# Schematic_v13.net
KiCad netlist of a schematic drawn in EAGLE
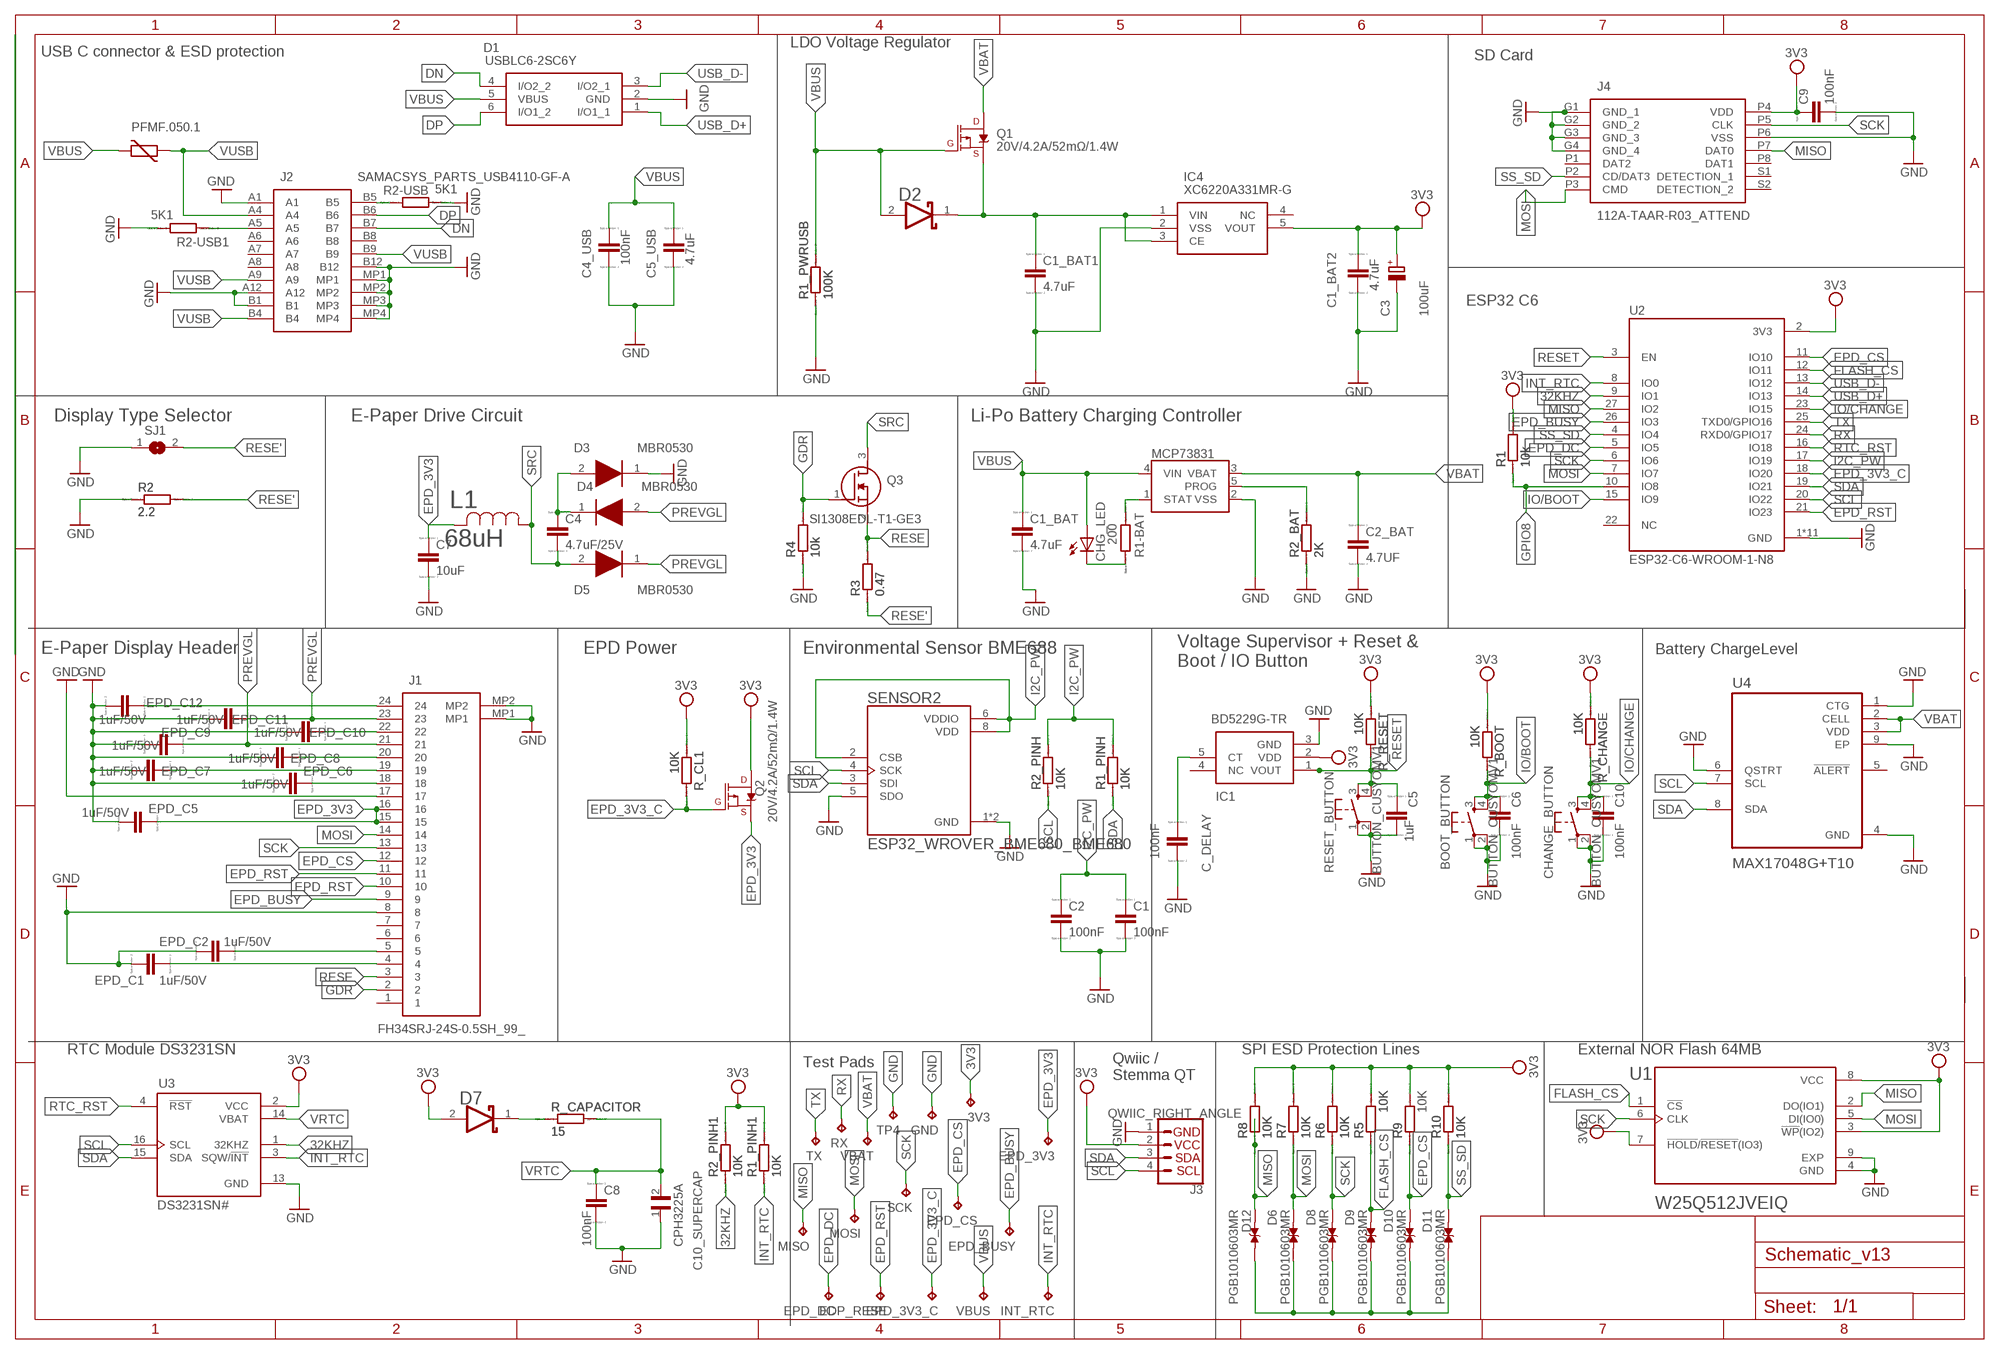
[diagram p0: schematic, sheet 1]

(export (version "E")
  (design (tool "Eeschema 10.0.6"))
  (components
    (comp (ref "3V3")
      (value "TPTP20R")
      (footprint "eagle-import:TP20R")
      (libsource (lib "eagle-import") (part "TPTP20R"))
    )
    (comp (ref "BOOT_BUTTON")
      (value "BUTTON_CUSYOMV1")
      (footprint "eagle-import:MYBUTTON")
      (libsource (lib "eagle-import") (part "BUTTON_CUSYOMV1"))
    )
    (comp (ref "C1")
      (value "100nF")
      (footprint "eagle-import:ESP32_WROVER_EAGLE-LTSPICE_C0402")
      (libsource (lib "eagle-import") (part "ESP32_WROVER_EAGLE-LTSPICE_CC0402"))
    )
    (comp (ref "C1_BAT")
      (value "4.7uF")
      (footprint "eagle-import:ESP32_WROVER_EAGLE-LTSPICE_C0402")
      (libsource (lib "eagle-import") (part "ESP32_WROVER_EAGLE-LTSPICE_CC0402"))
    )
    (comp (ref "C1_BAT1")
      (value "4.7uF")
      (footprint "eagle-import:ESP32_WROVER_EAGLE-LTSPICE_C0402")
      (libsource (lib "eagle-import") (part "ESP32_WROVER_EAGLE-LTSPICE_CC0402"))
    )
    (comp (ref "C1_BAT2")
      (value "4.7uF")
      (footprint "eagle-import:ESP32_WROVER_EAGLE-LTSPICE_C0402")
      (libsource (lib "eagle-import") (part "ESP32_WROVER_EAGLE-LTSPICE_CC0402"))
    )
    (comp (ref "C2")
      (value "100nF")
      (footprint "eagle-import:ESP32_WROVER_EAGLE-LTSPICE_C0402")
      (libsource (lib "eagle-import") (part "ESP32_WROVER_EAGLE-LTSPICE_CC0402"))
    )
    (comp (ref "C2_BAT")
      (value "4.7UF")
      (footprint "eagle-import:ESP32_WROVER_EAGLE-LTSPICE_C0402")
      (libsource (lib "eagle-import") (part "ESP32_WROVER_EAGLE-LTSPICE_CC0402"))
    )
    (comp (ref "C3")
      (value "100uF")
      (footprint "eagle-import:RCL_CT3528")
      (libsource (lib "eagle-import") (part "RCL_CPOL-EUCT3528"))
    )
    (comp (ref "C4")
      (value "4.7uF/25V")
      (footprint "eagle-import:ESP32_WROVER_EAGLE-LTSPICE_C0402")
      (libsource (lib "eagle-import") (part "ESP32_WROVER_EAGLE-LTSPICE_CC0402"))
    )
    (comp (ref "C4_USB")
      (value "100nF")
      (footprint "eagle-import:ESP32_WROVER_EAGLE-LTSPICE_C0402")
      (libsource (lib "eagle-import") (part "ESP32_WROVER_EAGLE-LTSPICE_CC0402"))
    )
    (comp (ref "C5")
      (value "1uF")
      (footprint "eagle-import:ESP32_WROVER_EAGLE-LTSPICE_C0402")
      (libsource (lib "eagle-import") (part "ESP32_WROVER_EAGLE-LTSPICE_CC0402"))
    )
    (comp (ref "C5_USB")
      (value "4.7uF")
      (footprint "eagle-import:ESP32_WROVER_EAGLE-LTSPICE_C0402")
      (libsource (lib "eagle-import") (part "ESP32_WROVER_EAGLE-LTSPICE_CC0402"))
    )
    (comp (ref "C6")
      (value "100nF")
      (footprint "eagle-import:ESP32_WROVER_EAGLE-LTSPICE_C0402")
      (libsource (lib "eagle-import") (part "ESP32_WROVER_EAGLE-LTSPICE_CC0402"))
    )
    (comp (ref "C7")
      (value "10uF")
      (footprint "eagle-import:ESP32_WROVER_EAGLE-LTSPICE_C0402")
      (libsource (lib "eagle-import") (part "ESP32_WROVER_EAGLE-LTSPICE_CC0402"))
    )
    (comp (ref "C8")
      (value "100nF")
      (footprint "eagle-import:ESP32_WROVER_EAGLE-LTSPICE_C0402")
      (libsource (lib "eagle-import") (part "ESP32_WROVER_EAGLE-LTSPICE_CC0402"))
    )
    (comp (ref "C9")
      (value "100nF")
      (footprint "eagle-import:ESP32_WROVER_EAGLE-LTSPICE_C0402")
      (libsource (lib "eagle-import") (part "ESP32_WROVER_EAGLE-LTSPICE_CC0402"))
    )
    (comp (ref "C10")
      (value "100nF")
      (footprint "eagle-import:ESP32_WROVER_EAGLE-LTSPICE_C0402")
      (libsource (lib "eagle-import") (part "ESP32_WROVER_EAGLE-LTSPICE_CC0402"))
    )
    (comp (ref "C10_SUPERCAP")
      (value "CPH3225A")
      (footprint "eagle-import:CAPCP3225X100N")
      (fields (field (name "MF") "Seiko Instruments"))
      (libsource (lib "eagle-import") (part "CPH3225A"))
    )
    (comp (ref "CHANGE_BUTTON")
      (value "BUTTON_CUSYOMV1")
      (footprint "eagle-import:MYBUTTON")
      (libsource (lib "eagle-import") (part "BUTTON_CUSYOMV1"))
    )
    (comp (ref "CHG_LED")
      (value "ADAFRUIT_LEDCHIP-LED0603")
      (footprint "eagle-import:ADAFRUIT_CHIP-LED0603")
      (libsource (lib "eagle-import") (part "ADAFRUIT_LEDCHIP-LED0603"))
    )
    (comp (ref "C_DELAY")
      (value "100nF")
      (footprint "eagle-import:ESP32_WROVER_EAGLE-LTSPICE_C0402")
      (libsource (lib "eagle-import") (part "ESP32_WROVER_EAGLE-LTSPICE_CC0402"))
    )
    (comp (ref "D1")
      (value "USBLC6-2SC6Y")
      (footprint "eagle-import:SOT95P280X145-6N")
      (fields (field (name "MF") "STMicroelectronics"))
      (libsource (lib "eagle-import") (part "USBLC6-2SC6Y"))
    )
    (comp (ref "D2")
      (value "ESP32_WROVER_AVX---SD0805S020S1R0_AVX_SD0805S020S1R0_0_0AVX_SD0805S020S1R0_0_0")
      (footprint "eagle-import:ESP32_WROVER_AVX---SD0805S020S1R0_AVX_SD0805S020S1R0_0")
      (fields
        (field (name "DIGIKEY_PART_NUMBER") "478-7800-1-ND")
        (field (name "MF") "AVX")
        (field (name "MOUSER_PART_NUMBER") "581-SD0805S020S1R0")
      )
      (libsource (lib "eagle-import") (part "ESP32_WROVER_AVX---SD0805S020S1R0_AVX_SD0805S020S1R0_0_0AVX_SD0805S020S1R0_0_0"))
    )
    (comp (ref "D3")
      (value "MBR0530")
      (footprint "eagle-import:SOD3716X135N")
      (fields (field (name "MF") "ON Semiconductor"))
      (libsource (lib "eagle-import") (part "MBR0530"))
    )
    (comp (ref "D4")
      (value "MBR0530")
      (footprint "eagle-import:SOD3716X135N")
      (fields (field (name "MF") "ON Semiconductor"))
      (libsource (lib "eagle-import") (part "MBR0530"))
    )
    (comp (ref "D5")
      (value "MBR0530")
      (footprint "eagle-import:SOD3716X135N")
      (fields (field (name "MF") "ON Semiconductor"))
      (libsource (lib "eagle-import") (part "MBR0530"))
    )
    (comp (ref "D6")
      (value "PGB1010603MR")
      (footprint "eagle-import:DIOC1608X36N")
      (fields (field (name "MF") "Littelfuse Inc."))
      (libsource (lib "eagle-import") (part "PGB1010603MR"))
    )
    (comp (ref "D7")
      (value "ESP32_WROVER_AVX---SD0805S020S1R0_AVX_SD0805S020S1R0_0_0AVX_SD0805S020S1R0_0_0")
      (footprint "eagle-import:ESP32_WROVER_AVX---SD0805S020S1R0_AVX_SD0805S020S1R0_0")
      (fields
        (field (name "DIGIKEY_PART_NUMBER") "478-7800-1-ND")
        (field (name "MF") "AVX")
        (field (name "MOUSER_PART_NUMBER") "581-SD0805S020S1R0")
      )
      (libsource (lib "eagle-import") (part "ESP32_WROVER_AVX---SD0805S020S1R0_AVX_SD0805S020S1R0_0_0AVX_SD0805S020S1R0_0_0"))
    )
    (comp (ref "D8")
      (value "PGB1010603MR")
      (footprint "eagle-import:DIOC1608X36N")
      (fields (field (name "MF") "Littelfuse Inc."))
      (libsource (lib "eagle-import") (part "PGB1010603MR"))
    )
    (comp (ref "D9")
      (value "PGB1010603MR")
      (footprint "eagle-import:DIOC1608X36N")
      (fields (field (name "MF") "Littelfuse Inc."))
      (libsource (lib "eagle-import") (part "PGB1010603MR"))
    )
    (comp (ref "D10")
      (value "PGB1010603MR")
      (footprint "eagle-import:DIOC1608X36N")
      (fields (field (name "MF") "Littelfuse Inc."))
      (libsource (lib "eagle-import") (part "PGB1010603MR"))
    )
    (comp (ref "D11")
      (value "PGB1010603MR")
      (footprint "eagle-import:DIOC1608X36N")
      (fields (field (name "MF") "Littelfuse Inc."))
      (libsource (lib "eagle-import") (part "PGB1010603MR"))
    )
    (comp (ref "D12")
      (value "PGB1010603MR")
      (footprint "eagle-import:DIOC1608X36N")
      (fields (field (name "MF") "Littelfuse Inc."))
      (libsource (lib "eagle-import") (part "PGB1010603MR"))
    )
    (comp (ref "EDP_RESE")
      (value "TPTP20R")
      (footprint "eagle-import:TP20R")
      (libsource (lib "eagle-import") (part "TPTP20R"))
    )
    (comp (ref "EPD_3V3")
      (value "TPTP20R")
      (footprint "eagle-import:TP20R")
      (libsource (lib "eagle-import") (part "TPTP20R"))
    )
    (comp (ref "EPD_3V3_C")
      (value "TPTP20R")
      (footprint "eagle-import:TP20R")
      (libsource (lib "eagle-import") (part "TPTP20R"))
    )
    (comp (ref "EPD_BUSY")
      (value "TPTP20R")
      (footprint "eagle-import:TP20R")
      (libsource (lib "eagle-import") (part "TPTP20R"))
    )
    (comp (ref "EPD_C1")
      (value "1uF/50V")
      (footprint "eagle-import:ESP32_WROVER_EAGLE-LTSPICE_C0402")
      (libsource (lib "eagle-import") (part "ESP32_WROVER_EAGLE-LTSPICE_CC0402"))
    )
    (comp (ref "EPD_C2")
      (value "1uF/50V")
      (footprint "eagle-import:ESP32_WROVER_EAGLE-LTSPICE_C0402")
      (libsource (lib "eagle-import") (part "ESP32_WROVER_EAGLE-LTSPICE_CC0402"))
    )
    (comp (ref "EPD_C5")
      (value "1uF/50V")
      (footprint "eagle-import:ESP32_WROVER_EAGLE-LTSPICE_C0402")
      (libsource (lib "eagle-import") (part "ESP32_WROVER_EAGLE-LTSPICE_CC0402"))
    )
    (comp (ref "EPD_C6")
      (value "1uF/50V")
      (footprint "eagle-import:ESP32_WROVER_EAGLE-LTSPICE_C0402")
      (libsource (lib "eagle-import") (part "ESP32_WROVER_EAGLE-LTSPICE_CC0402"))
    )
    (comp (ref "EPD_C7")
      (value "1uF/50V")
      (footprint "eagle-import:ESP32_WROVER_EAGLE-LTSPICE_C0402")
      (libsource (lib "eagle-import") (part "ESP32_WROVER_EAGLE-LTSPICE_CC0402"))
    )
    (comp (ref "EPD_C8")
      (value "1uF/50V")
      (footprint "eagle-import:ESP32_WROVER_EAGLE-LTSPICE_C0402")
      (libsource (lib "eagle-import") (part "ESP32_WROVER_EAGLE-LTSPICE_CC0402"))
    )
    (comp (ref "EPD_C9")
      (value "1uF/50V")
      (footprint "eagle-import:ESP32_WROVER_EAGLE-LTSPICE_C0402")
      (libsource (lib "eagle-import") (part "ESP32_WROVER_EAGLE-LTSPICE_CC0402"))
    )
    (comp (ref "EPD_C10")
      (value "1uF/50V")
      (footprint "eagle-import:ESP32_WROVER_EAGLE-LTSPICE_C0402")
      (libsource (lib "eagle-import") (part "ESP32_WROVER_EAGLE-LTSPICE_CC0402"))
    )
    (comp (ref "EPD_C11")
      (value "1uF/50V")
      (footprint "eagle-import:ESP32_WROVER_EAGLE-LTSPICE_C0402")
      (libsource (lib "eagle-import") (part "ESP32_WROVER_EAGLE-LTSPICE_CC0402"))
    )
    (comp (ref "EPD_C12")
      (value "1uF/50V")
      (footprint "eagle-import:ESP32_WROVER_EAGLE-LTSPICE_C0402")
      (libsource (lib "eagle-import") (part "ESP32_WROVER_EAGLE-LTSPICE_CC0402"))
    )
    (comp (ref "EPD_CS")
      (value "TPTP20R")
      (footprint "eagle-import:TP20R")
      (libsource (lib "eagle-import") (part "TPTP20R"))
    )
    (comp (ref "EPD_DC")
      (value "TPTP20R")
      (footprint "eagle-import:TP20R")
      (libsource (lib "eagle-import") (part "TPTP20R"))
    )
    (comp (ref "GND")
      (value "TPTP20R")
      (footprint "eagle-import:TP20R")
      (libsource (lib "eagle-import") (part "TPTP20R"))
    )
    (comp (ref "IC1")
      (value "BD5229G-TR")
      (footprint "eagle-import:SOT95P280X120-5N")
      (fields (field (name "MOUSER_PART_NUMBER") "755-BD5229G-TR"))
      (libsource (lib "eagle-import") (part "BD5229G-TR"))
    )
    (comp (ref "IC4")
      (value "XC6220A331MR-G")
      (footprint "eagle-import:SOT95P280X120-5N")
      (fields (field (name "MOUSER_PART_NUMBER") "865-XC6220A331MR-G"))
      (libsource (lib "eagle-import") (part "XC6220A331MR-G"))
    )
    (comp (ref "INT_RTC")
      (value "TPTP20R")
      (footprint "eagle-import:TP20R")
      (libsource (lib "eagle-import") (part "TPTP20R"))
    )
    (comp (ref "J1")
      (value "FH34SRJ-24S-0.5SH_99_")
      (footprint "eagle-import:FH34SRJ24S05SH99")
      (fields
        (field (name "MANUFACTURER_PART_NUMBER") "FH34SRJ-24S-0.5SH(99)")
        (field (name "MOUSER_PART_NUMBER") "798-FH34SRJ24S05SH99")
      )
      (libsource (lib "eagle-import") (part "FH34SRJ-24S-0.5SH_99_"))
    )
    (comp (ref "J2")
      (value "SAMACSYS_PARTS_USB4110-GF-A")
      (footprint "eagle-import:SAMACSYS_PARTS_USB4110GFA")
      (fields
        (field (name "MANUFACTURER_PART_NUMBER") "USB4110-GF-A")
        (field (name "MOUSER_PART_NUMBER") "640-USB4110-GF-A")
      )
      (libsource (lib "eagle-import") (part "SAMACSYS_PARTS_USB4110-GF-A"))
    )
    (comp (ref "J3")
      (value "QWIIC_RIGHT_ANGLE")
      (footprint "eagle-import:JST04_1MM_RA")
      (libsource (lib "eagle-import") (part "QWIIC_CONNECTORJS-1MM"))
    )
    (comp (ref "J4")
      (value "112A-TAAR-R03_ATTEND")
      (footprint "eagle-import:112ATAARR03ATTEND")
      (fields (field (name "MANUFACTURER_PART_NUMBER") "112A-TAAR-R03 ATTEND"))
      (libsource (lib "eagle-import") (part "112A-TAAR-R03_ATTEND"))
    )
    (comp (ref "L1")
      (value "68uH")
      (footprint "eagle-import:IND_4828-WE-TPC_WRE")
      (fields
        (field (name "MANUFACTURER_PART_NUMBER") "744043680")
        (field (name "COPYRIGHT") "Copyright (C) 2024 Ultra Librarian. All rights reserved.")
      )
      (libsource (lib "eagle-import") (part "744043680IND_4828-WE-TPC_WRE"))
    )
    (comp (ref "MCP73831")
      (value "ESP32_WROVER_SPARKFUN-IC-POWER_MCP73831")
      (footprint "eagle-import:ESP32_WROVER_SPARKFUN-IC-POWER_SOT23-5")
      (libsource (lib "eagle-import") (part "ESP32_WROVER_SPARKFUN-IC-POWER_MCP73831"))
    )
    (comp (ref "MISO")
      (value "TPTP20R")
      (footprint "eagle-import:TP20R")
      (libsource (lib "eagle-import") (part "TPTP20R"))
    )
    (comp (ref "MOSI")
      (value "TPTP20R")
      (footprint "eagle-import:TP20R")
      (libsource (lib "eagle-import") (part "TPTP20R"))
    )
    (comp (ref "PFMF.050.1")
      (value "ESP32C6_VARISTORCN1812")
      (footprint "eagle-import:ESP32C6_VARISTOR_CT_CN1812")
      (libsource (lib "eagle-import") (part "ESP32C6_VARISTORCN1812"))
    )
    (comp (ref "Q1")
      (value "20V/4.2A/52mΩ/1.4W")
      (footprint "eagle-import:ESP32_WROVER_SPARKFUN-DISCRETESEMI_SOT23-3")
      (libsource (lib "eagle-import") (part "ESP32_WROVER_SPARKFUN-DISCRETESEMI_MOSFET_PCH-DMG2305UX-7"))
    )
    (comp (ref "Q2")
      (value "20V/4.2A/52mΩ/1.4W")
      (footprint "eagle-import:ESP32_WROVER_SPARKFUN-DISCRETESEMI_SOT23-3")
      (libsource (lib "eagle-import") (part "ESP32_WROVER_SPARKFUN-DISCRETESEMI_MOSFET_PCH-DMG2305UX-7"))
    )
    (comp (ref "Q3")
      (value "SI1308EDL-T1-GE3")
      (footprint "eagle-import:SOT65P210X110-3N")
      (fields (field (name "MF") "Vishay Siliconix"))
      (libsource (lib "eagle-import") (part "SI1308EDL-T1-GE3"))
    )
    (comp (ref "R1")
      (value "10k")
      (footprint "eagle-import:ESP32_WROVER_EAGLE-LTSPICE_R0402")
      (libsource (lib "eagle-import") (part "ESP32_WROVER_EAGLE-LTSPICE_RR0402"))
    )
    (comp (ref "R1-BAT")
      (value "200")
      (footprint "eagle-import:ESP32_WROVER_EAGLE-LTSPICE_R0402")
      (libsource (lib "eagle-import") (part "ESP32_WROVER_EAGLE-LTSPICE_RR0402"))
    )
    (comp (ref "R1_PINH")
      (value "10K")
      (footprint "eagle-import:ESP32_WROVER_EAGLE-LTSPICE_R0402")
      (libsource (lib "eagle-import") (part "ESP32_WROVER_EAGLE-LTSPICE_RR0402"))
    )
    (comp (ref "R1_PINH1")
      (value "10K")
      (footprint "eagle-import:ESP32_WROVER_EAGLE-LTSPICE_R0402")
      (libsource (lib "eagle-import") (part "ESP32_WROVER_EAGLE-LTSPICE_RR0402"))
    )
    (comp (ref "R1_PWRUSB")
      (value "100K")
      (footprint "eagle-import:ESP32_WROVER_EAGLE-LTSPICE_R0402")
      (libsource (lib "eagle-import") (part "ESP32_WROVER_EAGLE-LTSPICE_RR0402"))
    )
    (comp (ref "R2")
      (value "2.2")
      (footprint "eagle-import:ESP32_WROVER_EAGLE-LTSPICE_R0402")
      (libsource (lib "eagle-import") (part "ESP32_WROVER_EAGLE-LTSPICE_RR0402"))
    )
    (comp (ref "R2-USB")
      (value "5K1")
      (footprint "eagle-import:ESP32_WROVER_EAGLE-LTSPICE_R0402")
      (libsource (lib "eagle-import") (part "ESP32_WROVER_EAGLE-LTSPICE_RR0402"))
    )
    (comp (ref "R2-USB1")
      (value "5K1")
      (footprint "eagle-import:ESP32_WROVER_EAGLE-LTSPICE_R0402")
      (libsource (lib "eagle-import") (part "ESP32_WROVER_EAGLE-LTSPICE_RR0402"))
    )
    (comp (ref "R2_BAT")
      (value "2K")
      (footprint "eagle-import:ESP32_WROVER_EAGLE-LTSPICE_R0402")
      (libsource (lib "eagle-import") (part "ESP32_WROVER_EAGLE-LTSPICE_RR0402"))
    )
    (comp (ref "R2_PINH")
      (value "10K")
      (footprint "eagle-import:ESP32_WROVER_EAGLE-LTSPICE_R0402")
      (libsource (lib "eagle-import") (part "ESP32_WROVER_EAGLE-LTSPICE_RR0402"))
    )
    (comp (ref "R2_PINH1")
      (value "10K")
      (footprint "eagle-import:ESP32_WROVER_EAGLE-LTSPICE_R0402")
      (libsource (lib "eagle-import") (part "ESP32_WROVER_EAGLE-LTSPICE_RR0402"))
    )
    (comp (ref "R3")
      (value "0.47")
      (footprint "eagle-import:ESP32_WROVER_EAGLE-LTSPICE_R0402")
      (libsource (lib "eagle-import") (part "ESP32_WROVER_EAGLE-LTSPICE_RR0402"))
    )
    (comp (ref "R4")
      (value "10k")
      (footprint "eagle-import:ESP32_WROVER_EAGLE-LTSPICE_R0402")
      (libsource (lib "eagle-import") (part "ESP32_WROVER_EAGLE-LTSPICE_RR0402"))
    )
    (comp (ref "R5")
      (value "10K")
      (footprint "eagle-import:ESP32_WROVER_EAGLE-LTSPICE_R0402")
      (libsource (lib "eagle-import") (part "ESP32_WROVER_EAGLE-LTSPICE_RR0402"))
    )
    (comp (ref "R6")
      (value "10K")
      (footprint "eagle-import:ESP32_WROVER_EAGLE-LTSPICE_R0402")
      (libsource (lib "eagle-import") (part "ESP32_WROVER_EAGLE-LTSPICE_RR0402"))
    )
    (comp (ref "R7")
      (value "10K")
      (footprint "eagle-import:ESP32_WROVER_EAGLE-LTSPICE_R0402")
      (libsource (lib "eagle-import") (part "ESP32_WROVER_EAGLE-LTSPICE_RR0402"))
    )
    (comp (ref "R8")
      (value "10K")
      (footprint "eagle-import:ESP32_WROVER_EAGLE-LTSPICE_R0402")
      (libsource (lib "eagle-import") (part "ESP32_WROVER_EAGLE-LTSPICE_RR0402"))
    )
    (comp (ref "R9")
      (value "10K")
      (footprint "eagle-import:ESP32_WROVER_EAGLE-LTSPICE_R0402")
      (libsource (lib "eagle-import") (part "ESP32_WROVER_EAGLE-LTSPICE_RR0402"))
    )
    (comp (ref "R10")
      (value "10K")
      (footprint "eagle-import:ESP32_WROVER_EAGLE-LTSPICE_R0402")
      (libsource (lib "eagle-import") (part "ESP32_WROVER_EAGLE-LTSPICE_RR0402"))
    )
    (comp (ref "RESET_BUTTON")
      (value "BUTTON_CUSYOMV1")
      (footprint "eagle-import:MYBUTTON")
      (libsource (lib "eagle-import") (part "BUTTON_CUSYOMV1"))
    )
    (comp (ref "RX")
      (value "TPTP20R")
      (footprint "eagle-import:TP20R")
      (libsource (lib "eagle-import") (part "TPTP20R"))
    )
    (comp (ref "R_BOOT")
      (value "10K")
      (footprint "eagle-import:ESP32_WROVER_EAGLE-LTSPICE_R0402")
      (libsource (lib "eagle-import") (part "ESP32_WROVER_EAGLE-LTSPICE_RR0402"))
    )
    (comp (ref "R_CAPACITOR")
      (value "15")
      (footprint "eagle-import:ESP32_WROVER_EAGLE-LTSPICE_R0402")
      (libsource (lib "eagle-import") (part "ESP32_WROVER_EAGLE-LTSPICE_RR0402"))
    )
    (comp (ref "R_CHANGE")
      (value "10K")
      (footprint "eagle-import:ESP32_WROVER_EAGLE-LTSPICE_R0402")
      (libsource (lib "eagle-import") (part "ESP32_WROVER_EAGLE-LTSPICE_RR0402"))
    )
    (comp (ref "R_CL1")
      (value "10K")
      (footprint "eagle-import:ESP32_WROVER_EAGLE-LTSPICE_R0402")
      (libsource (lib "eagle-import") (part "ESP32_WROVER_EAGLE-LTSPICE_RR0402"))
    )
    (comp (ref "R_RESET")
      (value "10K")
      (footprint "eagle-import:ESP32_WROVER_EAGLE-LTSPICE_R0402")
      (libsource (lib "eagle-import") (part "ESP32_WROVER_EAGLE-LTSPICE_RR0402"))
    )
    (comp (ref "SCK")
      (value "TPTP20R")
      (footprint "eagle-import:TP20R")
      (libsource (lib "eagle-import") (part "TPTP20R"))
    )
    (comp (ref "SENSOR2")
      (value "ESP32_WROVER_BME680_BME680")
      (footprint "eagle-import:ESP32_WROVER_BME680_PSON80P300X300X100-8N")
      (fields (field (name "MF") "Bosch Sensortec") (field (name "MP") "BME680"))
      (libsource (lib "eagle-import") (part "ESP32_WROVER_BME680_BME680"))
    )
    (comp (ref "SJ1") (value "SJ") (footprint "eagle-import:SJ") (libsource (lib "eagle-import") (part "SJ")))
    (comp (ref "TP4")
      (value "TPTP20R")
      (footprint "eagle-import:TP20R")
      (libsource (lib "eagle-import") (part "TPTP20R"))
    )
    (comp (ref "TX")
      (value "TPTP20R")
      (footprint "eagle-import:TP20R")
      (libsource (lib "eagle-import") (part "TPTP20R"))
    )
    (comp (ref "U1")
      (value "W25Q512JVEIQ")
      (footprint "eagle-import:SON127P600X800X80-9N")
      (fields (field (name "MF") "Winbond Electronics"))
      (libsource (lib "eagle-import") (part "W25Q512JVEIQ"))
    )
    (comp (ref "U2")
      (value "ESP32-C6-WROOM-1-N8")
      (footprint "eagle-import:XCVR_ESP32-C6-WROOM-1-N8")
      (fields (field (name "MF") "Espressif Systems"))
      (libsource (lib "eagle-import") (part "ESP32-C6-WROOM-1-N8"))
    )
    (comp (ref "U3")
      (value "DS3231SN#")
      (footprint "eagle-import:SOIC127P1032X265-16N")
      (fields (field (name "MF") "Analog Devices"))
      (libsource (lib "eagle-import") (part "DS3231SN#"))
    )
    (comp (ref "U4")
      (value "MAX17048G+T10")
      (footprint "eagle-import:SON50P200X200X80-9N")
      (fields (field (name "MF") "Analog Devices"))
      (libsource (lib "eagle-import") (part "MAX17048G+T10"))
    )
    (comp (ref "VBAT")
      (value "TPTP20R")
      (footprint "eagle-import:TP20R")
      (libsource (lib "eagle-import") (part "TPTP20R"))
    )
    (comp (ref "VBUS")
      (value "TPTP20R")
      (footprint "eagle-import:TP20R")
      (libsource (lib "eagle-import") (part "TPTP20R"))
    )
  )
  (nets
    (net (code "1") (name "3V3") (class "Default")
      (node (ref "3V3") (pin "TP") (pinfunction "TP_TP") (pintype "input"))
      (node (ref "C1_BAT2") (pin "1") (pinfunction "1_1") (pintype "passive"))
      (node (ref "C3") (pin "+") (pinfunction "+_+") (pintype "passive"))
      (node (ref "C9") (pin "1") (pinfunction "1_1") (pintype "passive"))
      (node (ref "D7") (pin "2") (pinfunction "ANODE_2") (pintype "bidirectional"))
      (node (ref "IC1") (pin "2") (pinfunction "VDD_2") (pintype "bidirectional"))
      (node (ref "IC4") (pin "5") (pinfunction "VOUT_5") (pintype "bidirectional"))
      (node (ref "J3") (pin "2") (pinfunction "2_2") (pintype "power_in"))
      (node (ref "J4") (pin "P4") (pinfunction "VDD_P4") (pintype "bidirectional"))
      (node (ref "Q2") (pin "3") (pinfunction "D_3") (pintype "bidirectional"))
      (node (ref "R1") (pin "2") (pinfunction "2_2") (pintype "passive"))
      (node (ref "R10") (pin "2") (pinfunction "2_2") (pintype "passive"))
      (node (ref "R1_PINH1") (pin "2") (pinfunction "2_2") (pintype "passive"))
      (node (ref "R2_PINH1") (pin "2") (pinfunction "2_2") (pintype "passive"))
      (node (ref "R5") (pin "2") (pinfunction "2_2") (pintype "passive"))
      (node (ref "R6") (pin "2") (pinfunction "2_2") (pintype "passive"))
      (node (ref "R7") (pin "2") (pinfunction "2_2") (pintype "passive"))
      (node (ref "R8") (pin "2") (pinfunction "2_2") (pintype "passive"))
      (node (ref "R9") (pin "2") (pinfunction "2_2") (pintype "passive"))
      (node (ref "R_BOOT") (pin "1") (pinfunction "1_1") (pintype "passive"))
      (node (ref "R_CHANGE") (pin "1") (pinfunction "1_1") (pintype "passive"))
      (node (ref "R_CL1") (pin "1") (pinfunction "1_1") (pintype "passive"))
      (node (ref "R_RESET") (pin "1") (pinfunction "1_1") (pintype "passive"))
      (node (ref "U1") (pin "3") (pinfunction "~{WP}(IO2)_3") (pintype "bidirectional"))
      (node (ref "U1") (pin "7") (pinfunction "~{HOLD}/~{RESET}(IO3)_7") (pintype "bidirectional"))
      (node (ref "U1") (pin "8") (pinfunction "VCC_8") (pintype "power_in"))
      (node (ref "U2") (pin "2") (pinfunction "3V3_2") (pintype "power_in"))
      (node (ref "U3") (pin "2") (pinfunction "VCC_2") (pintype "power_in"))
    )
    (net (code "2") (name "32KHZ") (class "Default")
      (node (ref "R2_PINH1") (pin "1") (pinfunction "1_1") (pintype "passive"))
      (node (ref "U2") (pin "9") (pinfunction "IO1_9") (pintype "bidirectional"))
      (node (ref "U3") (pin "1") (pinfunction "32KHZ_1") (pintype "output"))
    )
    (net (code "3") (name "DN") (class "Default")
      (node (ref "D1") (pin "4") (pinfunction "I/O2_2_4") (pintype "bidirectional"))
      (node (ref "J2") (pin "B7") (pinfunction "B7_B7") (pintype "bidirectional"))
    )
    (net (code "4") (name "DP") (class "Default")
      (node (ref "D1") (pin "6") (pinfunction "I/O1_2_6") (pintype "bidirectional"))
      (node (ref "J2") (pin "B6") (pinfunction "B6_B6") (pintype "bidirectional"))
    )
    (net (code "5") (name "EPD_3V3") (class "Default")
      (node (ref "C7") (pin "1") (pinfunction "1_1") (pintype "passive"))
      (node (ref "EPD_3V3") (pin "TP") (pinfunction "TP_TP") (pintype "input"))
      (node (ref "EPD_C5") (pin "1") (pinfunction "1_1") (pintype "passive"))
      (node (ref "J1") (pin "15") (pinfunction "15_15") (pintype "bidirectional"))
      (node (ref "J1") (pin "16") (pinfunction "16_16") (pintype "bidirectional"))
      (node (ref "L1") (pin "2") (pinfunction "2_2") (pintype "passive"))
      (node (ref "Q2") (pin "2") (pinfunction "S_2") (pintype "bidirectional"))
    )
    (net (code "6") (name "EPD_3V3_C") (class "Default")
      (node (ref "EPD_3V3_C") (pin "TP") (pinfunction "TP_TP") (pintype "input"))
      (node (ref "Q2") (pin "1") (pinfunction "G_1") (pintype "bidirectional"))
      (node (ref "R_CL1") (pin "2") (pinfunction "2_2") (pintype "passive"))
      (node (ref "U2") (pin "18") (pinfunction "IO20_18") (pintype "bidirectional"))
    )
    (net (code "7") (name "EPD_BUSY") (class "Default")
      (node (ref "EPD_BUSY") (pin "TP") (pinfunction "TP_TP") (pintype "input"))
      (node (ref "J1") (pin "9") (pinfunction "9_9") (pintype "bidirectional"))
      (node (ref "U2") (pin "26") (pinfunction "IO3_26") (pintype "bidirectional"))
    )
    (net (code "8") (name "EPD_CS") (class "Default")
      (node (ref "D10") (pin "1") (pinfunction "1_1") (pintype "passive"))
      (node (ref "EPD_CS") (pin "TP") (pinfunction "TP_TP") (pintype "input"))
      (node (ref "J1") (pin "12") (pinfunction "12_12") (pintype "bidirectional"))
      (node (ref "R9") (pin "1") (pinfunction "1_1") (pintype "passive"))
      (node (ref "U2") (pin "11") (pinfunction "IO10_11") (pintype "bidirectional"))
    )
    (net (code "9") (name "EPD_DC") (class "Default")
      (node (ref "EPD_DC") (pin "TP") (pinfunction "TP_TP") (pintype "input"))
      (node (ref "U2") (pin "5") (pinfunction "IO5_5") (pintype "bidirectional"))
    )
    (net (code "10") (name "EPD_RST") (class "Default")
      (node (ref "EDP_RESE") (pin "TP") (pinfunction "TP_TP") (pintype "input"))
      (node (ref "J1") (pin "10") (pinfunction "10_10") (pintype "bidirectional"))
      (node (ref "J1") (pin "11") (pinfunction "11_11") (pintype "bidirectional"))
      (node (ref "U2") (pin "21") (pinfunction "IO23_21") (pintype "bidirectional"))
    )
    (net (code "11") (name "FLASH_CS") (class "Default")
      (node (ref "D9") (pin "1") (pinfunction "1_1") (pintype "passive"))
      (node (ref "R5") (pin "1") (pinfunction "1_1") (pintype "passive"))
      (node (ref "U1") (pin "1") (pinfunction "~{CS}_1") (pintype "input"))
      (node (ref "U2") (pin "12") (pinfunction "IO11_12") (pintype "bidirectional"))
    )
    (net (code "12") (name "GDR") (class "Default")
      (node (ref "J1") (pin "2") (pinfunction "2_2") (pintype "bidirectional"))
      (node (ref "Q3") (pin "1") (pinfunction "G_1") (pintype "bidirectional"))
      (node (ref "R4") (pin "2") (pinfunction "2_2") (pintype "passive"))
    )
    (net (code "13") (name "GND") (class "Default")
      (node (ref "BOOT_BUTTON") (pin "1") (pinfunction "1_1") (pintype "passive"))
      (node (ref "BOOT_BUTTON") (pin "2") (pinfunction "2_2") (pintype "passive"))
      (node (ref "C1") (pin "2") (pinfunction "2_2") (pintype "passive"))
      (node (ref "C10") (pin "2") (pinfunction "2_2") (pintype "passive"))
      (node (ref "C10_SUPERCAP") (pin "1") (pinfunction "1_1") (pintype "passive"))
      (node (ref "C1_BAT") (pin "2") (pinfunction "2_2") (pintype "passive"))
      (node (ref "C1_BAT1") (pin "2") (pinfunction "2_2") (pintype "passive"))
      (node (ref "C1_BAT2") (pin "2") (pinfunction "2_2") (pintype "passive"))
      (node (ref "C2") (pin "2") (pinfunction "2_2") (pintype "passive"))
      (node (ref "C2_BAT") (pin "2") (pinfunction "2_2") (pintype "passive"))
      (node (ref "C3") (pin "-") (pinfunction "-_-") (pintype "passive"))
      (node (ref "C4_USB") (pin "2") (pinfunction "2_2") (pintype "passive"))
      (node (ref "C5") (pin "2") (pinfunction "2_2") (pintype "passive"))
      (node (ref "C5_USB") (pin "2") (pinfunction "2_2") (pintype "passive"))
      (node (ref "C6") (pin "2") (pinfunction "2_2") (pintype "passive"))
      (node (ref "C7") (pin "2") (pinfunction "2_2") (pintype "passive"))
      (node (ref "C8") (pin "2") (pinfunction "2_2") (pintype "passive"))
      (node (ref "C9") (pin "2") (pinfunction "2_2") (pintype "passive"))
      (node (ref "CHANGE_BUTTON") (pin "1") (pinfunction "1_1") (pintype "passive"))
      (node (ref "CHANGE_BUTTON") (pin "2") (pinfunction "2_2") (pintype "passive"))
      (node (ref "C_DELAY") (pin "2") (pinfunction "2_2") (pintype "passive"))
      (node (ref "D1") (pin "2") (pinfunction "GND_2") (pintype "bidirectional"))
      (node (ref "D3") (pin "1") (pinfunction "K_1") (pintype "bidirectional"))
      (node (ref "EPD_C1") (pin "2") (pinfunction "2_2") (pintype "passive"))
      (node (ref "EPD_C10") (pin "2") (pinfunction "2_2") (pintype "passive"))
      (node (ref "EPD_C11") (pin "2") (pinfunction "2_2") (pintype "passive"))
      (node (ref "EPD_C12") (pin "2") (pinfunction "2_2") (pintype "passive"))
      (node (ref "EPD_C2") (pin "2") (pinfunction "2_2") (pintype "passive"))
      (node (ref "EPD_C5") (pin "2") (pinfunction "2_2") (pintype "passive"))
      (node (ref "EPD_C6") (pin "2") (pinfunction "2_2") (pintype "passive"))
      (node (ref "EPD_C7") (pin "2") (pinfunction "2_2") (pintype "passive"))
      (node (ref "EPD_C8") (pin "2") (pinfunction "2_2") (pintype "passive"))
      (node (ref "EPD_C9") (pin "2") (pinfunction "2_2") (pintype "passive"))
      (node (ref "GND") (pin "TP") (pinfunction "TP_TP") (pintype "input"))
      (node (ref "IC1") (pin "3") (pinfunction "GND_3") (pintype "bidirectional"))
      (node (ref "IC4") (pin "2") (pinfunction "VSS_2") (pintype "bidirectional"))
      (node (ref "J1") (pin "17") (pinfunction "17_17") (pintype "bidirectional"))
      (node (ref "J1") (pin "8") (pinfunction "8_8") (pintype "bidirectional"))
      (node (ref "J1") (pin "MP1") (pinfunction "MP1_MP1") (pintype "bidirectional"))
      (node (ref "J1") (pin "MP2") (pinfunction "MP2_MP2") (pintype "bidirectional"))
      (node (ref "J2") (pin "A1") (pinfunction "A1_A1") (pintype "bidirectional"))
      (node (ref "J2") (pin "A12") (pinfunction "A12_A12") (pintype "bidirectional"))
      (node (ref "J2") (pin "B1") (pinfunction "B1_B1") (pintype "bidirectional"))
      (node (ref "J2") (pin "B12") (pinfunction "B12_B12") (pintype "bidirectional"))
      (node (ref "J2") (pin "MP1") (pinfunction "MP1_MP1") (pintype "bidirectional"))
      (node (ref "J2") (pin "MP2") (pinfunction "MP2_MP2") (pintype "bidirectional"))
      (node (ref "J2") (pin "MP3") (pinfunction "MP3_MP3") (pintype "bidirectional"))
      (node (ref "J2") (pin "MP4") (pinfunction "MP4_MP4") (pintype "bidirectional"))
      (node (ref "J3") (pin "1") (pinfunction "1_1") (pintype "power_in"))
      (node (ref "J4") (pin "G1") (pinfunction "GND_1_G1") (pintype "bidirectional"))
      (node (ref "J4") (pin "G2") (pinfunction "GND_2_G2") (pintype "bidirectional"))
      (node (ref "J4") (pin "G3") (pinfunction "GND_3_G3") (pintype "bidirectional"))
      (node (ref "J4") (pin "G4") (pinfunction "GND_4_G4") (pintype "bidirectional"))
      (node (ref "J4") (pin "P6") (pinfunction "VSS_P6") (pintype "bidirectional"))
      (node (ref "MCP73831") (pin "2") (pinfunction "VSS_2") (pintype "power_in"))
      (node (ref "R1_PWRUSB") (pin "1") (pinfunction "1_1") (pintype "passive"))
      (node (ref "R2") (pin "1") (pinfunction "1_1") (pintype "passive"))
      (node (ref "R2-USB") (pin "2") (pinfunction "2_2") (pintype "passive"))
      (node (ref "R2-USB1") (pin "1") (pinfunction "1_1") (pintype "passive"))
      (node (ref "R2_BAT") (pin "1") (pinfunction "1_1") (pintype "passive"))
      (node (ref "R4") (pin "1") (pinfunction "1_1") (pintype "passive"))
      (node (ref "RESET_BUTTON") (pin "1") (pinfunction "1_1") (pintype "passive"))
      (node (ref "RESET_BUTTON") (pin "2") (pinfunction "2_2") (pintype "passive"))
      (node (ref "SENSOR2") (pin "1") (pinfunction "GND_1") (pintype "power_in"))
      (node (ref "SENSOR2") (pin "5") (pinfunction "SDO_5") (pintype "bidirectional"))
      (node (ref "SENSOR2") (pin "7") (pinfunction "GND_7") (pintype "power_in"))
      (node (ref "SJ1") (pin "1") (pinfunction "1_1") (pintype "passive"))
      (node (ref "TP4") (pin "TP") (pinfunction "TP_TP") (pintype "input"))
      (node (ref "U1") (pin "4") (pinfunction "GND_4") (pintype "power_in"))
      (node (ref "U1") (pin "9") (pinfunction "EXP_9") (pintype "passive"))
      (node (ref "U2") (pin "1") (pinfunction "GND_1") (pintype "power_in"))
      (node (ref "U2") (pin "28") (pinfunction "GND_28") (pintype "power_in"))
      (node (ref "U2") (pin "29_1") (pinfunction "GND_29_1") (pintype "power_in"))
      (node (ref "U2") (pin "29_2") (pinfunction "GND_29_2") (pintype "power_in"))
      (node (ref "U2") (pin "29_3") (pinfunction "GND_29_3") (pintype "power_in"))
      (node (ref "U2") (pin "29_4") (pinfunction "GND_29_4") (pintype "power_in"))
      (node (ref "U2") (pin "29_5") (pinfunction "GND_29_5") (pintype "power_in"))
      (node (ref "U2") (pin "29_6") (pinfunction "GND_29_6") (pintype "power_in"))
      (node (ref "U2") (pin "29_7") (pinfunction "GND_29_7") (pintype "power_in"))
      (node (ref "U2") (pin "29_8") (pinfunction "GND_29_8") (pintype "power_in"))
      (node (ref "U2") (pin "29_9") (pinfunction "GND_29_9") (pintype "power_in"))
      (node (ref "U3") (pin "13") (pinfunction "GND_13") (pintype "power_in"))
      (node (ref "U4") (pin "1") (pinfunction "CTG_1") (pintype "power_in"))
      (node (ref "U4") (pin "4") (pinfunction "GND_4") (pintype "power_in"))
      (node (ref "U4") (pin "6") (pinfunction "QSTRT_6") (pintype "input"))
      (node (ref "U4") (pin "9") (pinfunction "EP_9") (pintype "power_in"))
    )
    (net (code "14") (name "GPIO8") (class "Default")
      (node (ref "R1") (pin "1") (pinfunction "1_1") (pintype "passive"))
      (node (ref "U2") (pin "10") (pinfunction "IO8_10") (pintype "bidirectional"))
    )
    (net (code "15") (name "I2C_PW") (class "Default")
      (node (ref "C1") (pin "1") (pinfunction "1_1") (pintype "passive"))
      (node (ref "C2") (pin "1") (pinfunction "1_1") (pintype "passive"))
      (node (ref "R1_PINH") (pin "2") (pinfunction "2_2") (pintype "passive"))
      (node (ref "R2_PINH") (pin "2") (pinfunction "2_2") (pintype "passive"))
      (node (ref "SENSOR2") (pin "2") (pinfunction "CSB_2") (pintype "input"))
      (node (ref "SENSOR2") (pin "6") (pinfunction "VDDIO_6") (pintype "power_in"))
      (node (ref "SENSOR2") (pin "8") (pinfunction "VDD_8") (pintype "power_in"))
      (node (ref "U2") (pin "17") (pinfunction "IO19_17") (pintype "bidirectional"))
    )
    (net (code "16") (name "INT_RTC") (class "Default")
      (node (ref "INT_RTC") (pin "TP") (pinfunction "TP_TP") (pintype "input"))
      (node (ref "R1_PINH1") (pin "1") (pinfunction "1_1") (pintype "passive"))
      (node (ref "U2") (pin "8") (pinfunction "IO0_8") (pintype "bidirectional"))
      (node (ref "U3") (pin "3") (pinfunction "SQW/~{INT}_3") (pintype "output"))
    )
    (net (code "17") (name "IO{slash}BOOT") (class "Default")
      (node (ref "BOOT_BUTTON") (pin "3") (pinfunction "3_3") (pintype "passive"))
      (node (ref "BOOT_BUTTON") (pin "4") (pinfunction "4_4") (pintype "passive"))
      (node (ref "C6") (pin "1") (pinfunction "1_1") (pintype "passive"))
      (node (ref "R_BOOT") (pin "2") (pinfunction "2_2") (pintype "passive"))
      (node (ref "U2") (pin "15") (pinfunction "IO9_15") (pintype "bidirectional"))
    )
    (net (code "18") (name "IO{slash}CHANGE") (class "Default")
      (node (ref "C10") (pin "1") (pinfunction "1_1") (pintype "passive"))
      (node (ref "CHANGE_BUTTON") (pin "3") (pinfunction "3_3") (pintype "passive"))
      (node (ref "CHANGE_BUTTON") (pin "4") (pinfunction "4_4") (pintype "passive"))
      (node (ref "R_CHANGE") (pin "2") (pinfunction "2_2") (pintype "passive"))
      (node (ref "U2") (pin "23") (pinfunction "IO15_23") (pintype "bidirectional"))
    )
    (net (code "19") (name "MISO") (class "Default")
      (node (ref "D12") (pin "1") (pinfunction "1_1") (pintype "passive"))
      (node (ref "J4") (pin "P7") (pinfunction "DAT0_P7") (pintype "bidirectional"))
      (node (ref "MISO") (pin "TP") (pinfunction "TP_TP") (pintype "input"))
      (node (ref "R8") (pin "1") (pinfunction "1_1") (pintype "passive"))
      (node (ref "U1") (pin "2") (pinfunction "DO(IO1)_2") (pintype "bidirectional"))
      (node (ref "U2") (pin "27") (pinfunction "IO2_27") (pintype "bidirectional"))
    )
    (net (code "20") (name "MOSI") (class "Default")
      (node (ref "D6") (pin "1") (pinfunction "1_1") (pintype "passive"))
      (node (ref "J1") (pin "14") (pinfunction "14_14") (pintype "bidirectional"))
      (node (ref "J4") (pin "P3") (pinfunction "CMD_P3") (pintype "bidirectional"))
      (node (ref "MOSI") (pin "TP") (pinfunction "TP_TP") (pintype "input"))
      (node (ref "R7") (pin "1") (pinfunction "1_1") (pintype "passive"))
      (node (ref "U1") (pin "5") (pinfunction "DI(IO0)_5") (pintype "bidirectional"))
      (node (ref "U2") (pin "7") (pinfunction "IO7_7") (pintype "bidirectional"))
    )
    (net (code "21") (name "Net-(CHG_LED-PadC)") (class "Default")
      (node (ref "CHG_LED") (pin "C") (pinfunction "C_C") (pintype "passive"))
      (node (ref "R1-BAT") (pin "1") (pinfunction "1_1") (pintype "passive"))
    )
    (net (code "22") (name "Net-(D2-CATHODE)") (class "Default")
      (node (ref "C1_BAT1") (pin "1") (pinfunction "1_1") (pintype "passive"))
      (node (ref "D2") (pin "1") (pinfunction "CATHODE_1") (pintype "bidirectional"))
      (node (ref "IC4") (pin "1") (pinfunction "VIN_1") (pintype "bidirectional"))
      (node (ref "IC4") (pin "3") (pinfunction "CE_3") (pintype "bidirectional"))
      (node (ref "Q1") (pin "2") (pinfunction "S_2") (pintype "bidirectional"))
    )
    (net (code "23") (name "Net-(D3-A)") (class "Default")
      (node (ref "C4") (pin "1") (pinfunction "1_1") (pintype "passive"))
      (node (ref "D3") (pin "2") (pinfunction "A_2") (pintype "bidirectional"))
      (node (ref "D4") (pin "1") (pinfunction "K_1") (pintype "bidirectional"))
    )
    (net (code "24") (name "Net-(D7-CATHODE)") (class "Default")
      (node (ref "D7") (pin "1") (pinfunction "CATHODE_1") (pintype "bidirectional"))
      (node (ref "R_CAPACITOR") (pin "1") (pinfunction "1_1") (pintype "passive"))
    )
    (net (code "25") (name "Net-(D10-Pad2)") (class "Default")
      (node (ref "D10") (pin "2") (pinfunction "2_2") (pintype "passive"))
      (node (ref "D11") (pin "2") (pinfunction "2_2") (pintype "passive"))
      (node (ref "D12") (pin "2") (pinfunction "2_2") (pintype "passive"))
      (node (ref "D6") (pin "2") (pinfunction "2_2") (pintype "passive"))
      (node (ref "D8") (pin "2") (pinfunction "2_2") (pintype "passive"))
      (node (ref "D9") (pin "2") (pinfunction "2_2") (pintype "passive"))
    )
    (net (code "26") (name "Net-(EPD_C1-Pad1)") (class "Default")
      (node (ref "EPD_C1") (pin "1") (pinfunction "1_1") (pintype "passive"))
      (node (ref "J1") (pin "4") (pinfunction "4_4") (pintype "bidirectional"))
    )
    (net (code "27") (name "Net-(EPD_C2-Pad1)") (class "Default")
      (node (ref "EPD_C2") (pin "1") (pinfunction "1_1") (pintype "passive"))
      (node (ref "J1") (pin "5") (pinfunction "5_5") (pintype "bidirectional"))
    )
    (net (code "28") (name "Net-(EPD_C6-Pad1)") (class "Default")
      (node (ref "EPD_C6") (pin "1") (pinfunction "1_1") (pintype "passive"))
      (node (ref "J1") (pin "18") (pinfunction "18_18") (pintype "bidirectional"))
    )
    (net (code "29") (name "Net-(EPD_C7-Pad1)") (class "Default")
      (node (ref "EPD_C7") (pin "1") (pinfunction "1_1") (pintype "passive"))
      (node (ref "J1") (pin "19") (pinfunction "19_19") (pintype "bidirectional"))
    )
    (net (code "30") (name "Net-(EPD_C8-Pad1)") (class "Default")
      (node (ref "EPD_C8") (pin "1") (pinfunction "1_1") (pintype "passive"))
      (node (ref "J1") (pin "20") (pinfunction "20_20") (pintype "bidirectional"))
    )
    (net (code "31") (name "Net-(EPD_C10-Pad1)") (class "Default")
      (node (ref "EPD_C10") (pin "1") (pinfunction "1_1") (pintype "passive"))
      (node (ref "J1") (pin "22") (pinfunction "22_22") (pintype "bidirectional"))
    )
    (net (code "32") (name "Net-(EPD_C12-Pad1)") (class "Default")
      (node (ref "EPD_C12") (pin "1") (pinfunction "1_1") (pintype "passive"))
      (node (ref "J1") (pin "24") (pinfunction "24_24") (pintype "bidirectional"))
    )
    (net (code "33") (name "Net-(IC1-CT)") (class "Default")
      (node (ref "C_DELAY") (pin "1") (pinfunction "1_1") (pintype "passive"))
      (node (ref "IC1") (pin "5") (pinfunction "CT_5") (pintype "bidirectional"))
    )
    (net (code "34") (name "Net-(J2-PadA5)") (class "Default")
      (node (ref "J2") (pin "A5") (pinfunction "A5_A5") (pintype "bidirectional"))
      (node (ref "R2-USB1") (pin "2") (pinfunction "2_2") (pintype "passive"))
    )
    (net (code "35") (name "Net-(J2-PadB5)") (class "Default")
      (node (ref "J2") (pin "B5") (pinfunction "B5_B5") (pintype "bidirectional"))
      (node (ref "R2-USB") (pin "1") (pinfunction "1_1") (pintype "passive"))
    )
    (net (code "36") (name "Net-(MCP73831-PROG)") (class "Default")
      (node (ref "MCP73831") (pin "5") (pinfunction "PROG_5") (pintype "input"))
      (node (ref "R2_BAT") (pin "2") (pinfunction "2_2") (pintype "passive"))
    )
    (net (code "37") (name "Net-(MCP73831-STAT)") (class "Default")
      (node (ref "MCP73831") (pin "1") (pinfunction "STAT_1") (pintype "output"))
      (node (ref "R1-BAT") (pin "2") (pinfunction "2_2") (pintype "passive"))
    )
    (net (code "38") (name "PREVGL") (class "Default")
      (node (ref "D4") (pin "2") (pinfunction "A_2") (pintype "bidirectional"))
      (node (ref "D5") (pin "1") (pinfunction "K_1") (pintype "bidirectional"))
      (node (ref "EPD_C11") (pin "1") (pinfunction "1_1") (pintype "passive"))
      (node (ref "EPD_C9") (pin "1") (pinfunction "1_1") (pintype "passive"))
      (node (ref "J1") (pin "21") (pinfunction "21_21") (pintype "bidirectional"))
      (node (ref "J1") (pin "23") (pinfunction "23_23") (pintype "bidirectional"))
    )
    (net (code "39") (name "RESE") (class "Default")
      (node (ref "J1") (pin "3") (pinfunction "3_3") (pintype "bidirectional"))
      (node (ref "Q3") (pin "2") (pinfunction "S_2") (pintype "bidirectional"))
      (node (ref "R3") (pin "2") (pinfunction "2_2") (pintype "passive"))
    )
    (net (code "40") (name "RESE'") (class "Default")
      (node (ref "R2") (pin "2") (pinfunction "2_2") (pintype "passive"))
      (node (ref "R3") (pin "1") (pinfunction "1_1") (pintype "passive"))
      (node (ref "SJ1") (pin "2") (pinfunction "2_2") (pintype "passive"))
    )
    (net (code "41") (name "RESET") (class "Default")
      (node (ref "C5") (pin "1") (pinfunction "1_1") (pintype "passive"))
      (node (ref "IC1") (pin "1") (pinfunction "VOUT_1") (pintype "bidirectional"))
      (node (ref "RESET_BUTTON") (pin "3") (pinfunction "3_3") (pintype "passive"))
      (node (ref "RESET_BUTTON") (pin "4") (pinfunction "4_4") (pintype "passive"))
      (node (ref "R_RESET") (pin "2") (pinfunction "2_2") (pintype "passive"))
      (node (ref "U2") (pin "3") (pinfunction "EN_3") (pintype "input"))
    )
    (net (code "42") (name "RTC_RST") (class "Default")
      (node (ref "U2") (pin "16") (pinfunction "IO18_16") (pintype "bidirectional"))
      (node (ref "U3") (pin "4") (pinfunction "~{RST}_4") (pintype "input"))
    )
    (net (code "43") (name "RX") (class "Default")
      (node (ref "RX") (pin "TP") (pinfunction "TP_TP") (pintype "input"))
      (node (ref "U2") (pin "24") (pinfunction "RXD0/GPIO17_24") (pintype "bidirectional"))
    )
    (net (code "44") (name "SCK") (class "Default")
      (node (ref "D8") (pin "1") (pinfunction "1_1") (pintype "passive"))
      (node (ref "J1") (pin "13") (pinfunction "13_13") (pintype "bidirectional"))
      (node (ref "J4") (pin "P5") (pinfunction "CLK_P5") (pintype "bidirectional"))
      (node (ref "R6") (pin "1") (pinfunction "1_1") (pintype "passive"))
      (node (ref "SCK") (pin "TP") (pinfunction "TP_TP") (pintype "input"))
      (node (ref "U1") (pin "6") (pinfunction "CLK_6") (pintype "input"))
      (node (ref "U2") (pin "6") (pinfunction "IO6_6") (pintype "bidirectional"))
    )
    (net (code "45") (name "SCL") (class "Default")
      (node (ref "J3") (pin "4") (pinfunction "4_4") (pintype "passive"))
      (node (ref "R2_PINH") (pin "1") (pinfunction "1_1") (pintype "passive"))
      (node (ref "SENSOR2") (pin "4") (pinfunction "SCK_4") (pintype "input"))
      (node (ref "U2") (pin "20") (pinfunction "IO22_20") (pintype "bidirectional"))
      (node (ref "U3") (pin "16") (pinfunction "SCL_16") (pintype "input"))
      (node (ref "U4") (pin "7") (pinfunction "SCL_7") (pintype "input"))
    )
    (net (code "46") (name "SDA") (class "Default")
      (node (ref "J3") (pin "3") (pinfunction "3_3") (pintype "passive"))
      (node (ref "R1_PINH") (pin "1") (pinfunction "1_1") (pintype "passive"))
      (node (ref "SENSOR2") (pin "3") (pinfunction "SDI_3") (pintype "bidirectional"))
      (node (ref "U2") (pin "19") (pinfunction "IO21_19") (pintype "bidirectional"))
      (node (ref "U3") (pin "15") (pinfunction "SDA_15") (pintype "bidirectional"))
      (node (ref "U4") (pin "8") (pinfunction "SDA_8") (pintype "bidirectional"))
    )
    (net (code "47") (name "SRC") (class "Default")
      (node (ref "C4") (pin "2") (pinfunction "2_2") (pintype "passive"))
      (node (ref "D5") (pin "2") (pinfunction "A_2") (pintype "bidirectional"))
      (node (ref "L1") (pin "1") (pinfunction "1_1") (pintype "passive"))
      (node (ref "Q3") (pin "3") (pinfunction "D_3") (pintype "bidirectional"))
    )
    (net (code "48") (name "SS_SD") (class "Default")
      (node (ref "D11") (pin "1") (pinfunction "1_1") (pintype "passive"))
      (node (ref "J4") (pin "P2") (pinfunction "CD/DAT3_P2") (pintype "bidirectional"))
      (node (ref "R10") (pin "1") (pinfunction "1_1") (pintype "passive"))
      (node (ref "U2") (pin "4") (pinfunction "IO4_4") (pintype "bidirectional"))
    )
    (net (code "49") (name "TX") (class "Default")
      (node (ref "TX") (pin "TP") (pinfunction "TP_TP") (pintype "input"))
      (node (ref "U2") (pin "25") (pinfunction "TXD0/GPIO16_25") (pintype "bidirectional"))
    )
    (net (code "50") (name "USB_D+") (class "Default")
      (node (ref "D1") (pin "1") (pinfunction "I/O1_1_1") (pintype "bidirectional"))
      (node (ref "U2") (pin "14") (pinfunction "IO13_14") (pintype "bidirectional"))
    )
    (net (code "51") (name "USB_D-") (class "Default")
      (node (ref "D1") (pin "3") (pinfunction "I/O2_1_3") (pintype "bidirectional"))
      (node (ref "U2") (pin "13") (pinfunction "IO12_13") (pintype "bidirectional"))
    )
    (net (code "52") (name "VBAT") (class "Default")
      (node (ref "C2_BAT") (pin "1") (pinfunction "1_1") (pintype "passive"))
      (node (ref "MCP73831") (pin "3") (pinfunction "VBAT_3") (pintype "power_in"))
      (node (ref "Q1") (pin "3") (pinfunction "D_3") (pintype "bidirectional"))
      (node (ref "U4") (pin "2") (pinfunction "CELL_2") (pintype "power_in"))
      (node (ref "U4") (pin "3") (pinfunction "VDD_3") (pintype "power_in"))
      (node (ref "VBAT") (pin "TP") (pinfunction "TP_TP") (pintype "input"))
    )
    (net (code "53") (name "VBUS") (class "Default")
      (node (ref "C1_BAT") (pin "1") (pinfunction "1_1") (pintype "passive"))
      (node (ref "C4_USB") (pin "1") (pinfunction "1_1") (pintype "passive"))
      (node (ref "C5_USB") (pin "1") (pinfunction "1_1") (pintype "passive"))
      (node (ref "CHG_LED") (pin "A") (pinfunction "A_A") (pintype "passive"))
      (node (ref "D1") (pin "5") (pinfunction "VBUS_5") (pintype "bidirectional"))
      (node (ref "D2") (pin "2") (pinfunction "ANODE_2") (pintype "bidirectional"))
      (node (ref "MCP73831") (pin "4") (pinfunction "VIN_4") (pintype "power_in"))
      (node (ref "PFMF.050.1") (pin "2") (pinfunction "2_2") (pintype "passive"))
      (node (ref "Q1") (pin "1") (pinfunction "G_1") (pintype "bidirectional"))
      (node (ref "R1_PWRUSB") (pin "2") (pinfunction "2_2") (pintype "passive"))
      (node (ref "VBUS") (pin "TP") (pinfunction "TP_TP") (pintype "input"))
    )
    (net (code "54") (name "VRTC") (class "Default")
      (node (ref "C10_SUPERCAP") (pin "2") (pinfunction "2_2") (pintype "passive"))
      (node (ref "C8") (pin "1") (pinfunction "1_1") (pintype "passive"))
      (node (ref "R_CAPACITOR") (pin "2") (pinfunction "2_2") (pintype "passive"))
      (node (ref "U3") (pin "14") (pinfunction "VBAT_14") (pintype "power_in"))
    )
    (net (code "55") (name "VUSB") (class "Default")
      (node (ref "J2") (pin "A4") (pinfunction "A4_A4") (pintype "bidirectional"))
      (node (ref "J2") (pin "A9") (pinfunction "A9_A9") (pintype "bidirectional"))
      (node (ref "J2") (pin "B4") (pinfunction "B4_B4") (pintype "bidirectional"))
      (node (ref "J2") (pin "B9") (pinfunction "B9_B9") (pintype "bidirectional"))
      (node (ref "PFMF.050.1") (pin "1") (pinfunction "1_1") (pintype "passive"))
    )
    (net (code "56") (name "unconnected-(IC1-NC-Pad4)") (class "Default")
      (node (ref "IC1") (pin "4") (pinfunction "NC_4") (pintype "no_connect"))
    )
    (net (code "57") (name "unconnected-(IC4-NC-Pad4)") (class "Default")
      (node (ref "IC4") (pin "4") (pinfunction "NC_4") (pintype "no_connect"))
    )
    (net (code "58") (name "unconnected-(J1-Pad1)") (class "Default")
      (node (ref "J1") (pin "1") (pinfunction "1_1") (pintype "bidirectional"))
    )
    (net (code "59") (name "unconnected-(J1-Pad6)") (class "Default")
      (node (ref "J1") (pin "6") (pinfunction "6_6") (pintype "bidirectional"))
    )
    (net (code "60") (name "unconnected-(J1-Pad7)") (class "Default")
      (node (ref "J1") (pin "7") (pinfunction "7_7") (pintype "bidirectional"))
    )
    (net (code "61") (name "unconnected-(J2-PadA6)") (class "Default")
      (node (ref "J2") (pin "A6") (pinfunction "A6_A6") (pintype "bidirectional"))
    )
    (net (code "62") (name "unconnected-(J2-PadA7)") (class "Default")
      (node (ref "J2") (pin "A7") (pinfunction "A7_A7") (pintype "bidirectional"))
    )
    (net (code "63") (name "unconnected-(J2-PadA8)") (class "Default")
      (node (ref "J2") (pin "A8") (pinfunction "A8_A8") (pintype "bidirectional"))
    )
    (net (code "64") (name "unconnected-(J2-PadB8)") (class "Default")
      (node (ref "J2") (pin "B8") (pinfunction "B8_B8") (pintype "bidirectional"))
    )
    (net (code "65") (name "unconnected-(J4-DAT1-PadP8)") (class "Default")
      (node (ref "J4") (pin "P8") (pinfunction "DAT1_P8") (pintype "bidirectional"))
    )
    (net (code "66") (name "unconnected-(J4-DAT2-PadP1)") (class "Default")
      (node (ref "J4") (pin "P1") (pinfunction "DAT2_P1") (pintype "bidirectional"))
    )
    (net (code "67") (name "unconnected-(J4-DETECTION_1-PadS1)") (class "Default")
      (node (ref "J4") (pin "S1") (pinfunction "DETECTION_1_S1") (pintype "bidirectional"))
    )
    (net (code "68") (name "unconnected-(J4-DETECTION_2-PadS2)") (class "Default")
      (node (ref "J4") (pin "S2") (pinfunction "DETECTION_2_S2") (pintype "bidirectional"))
    )
    (net (code "69") (name "unconnected-(U2-NC-Pad22)") (class "Default")
      (node (ref "U2") (pin "22") (pinfunction "NC_22") (pintype "no_connect"))
    )
    (net (code "70") (name "unconnected-(U4-~{ALERT}-Pad5)") (class "Default")
      (node (ref "U4") (pin "5") (pinfunction "~{ALERT}_5") (pintype "output"))
    )
  )
)
